# Arduino_extension_connectors.net
KiCad netlist of a schematic drawn in Altium Designer
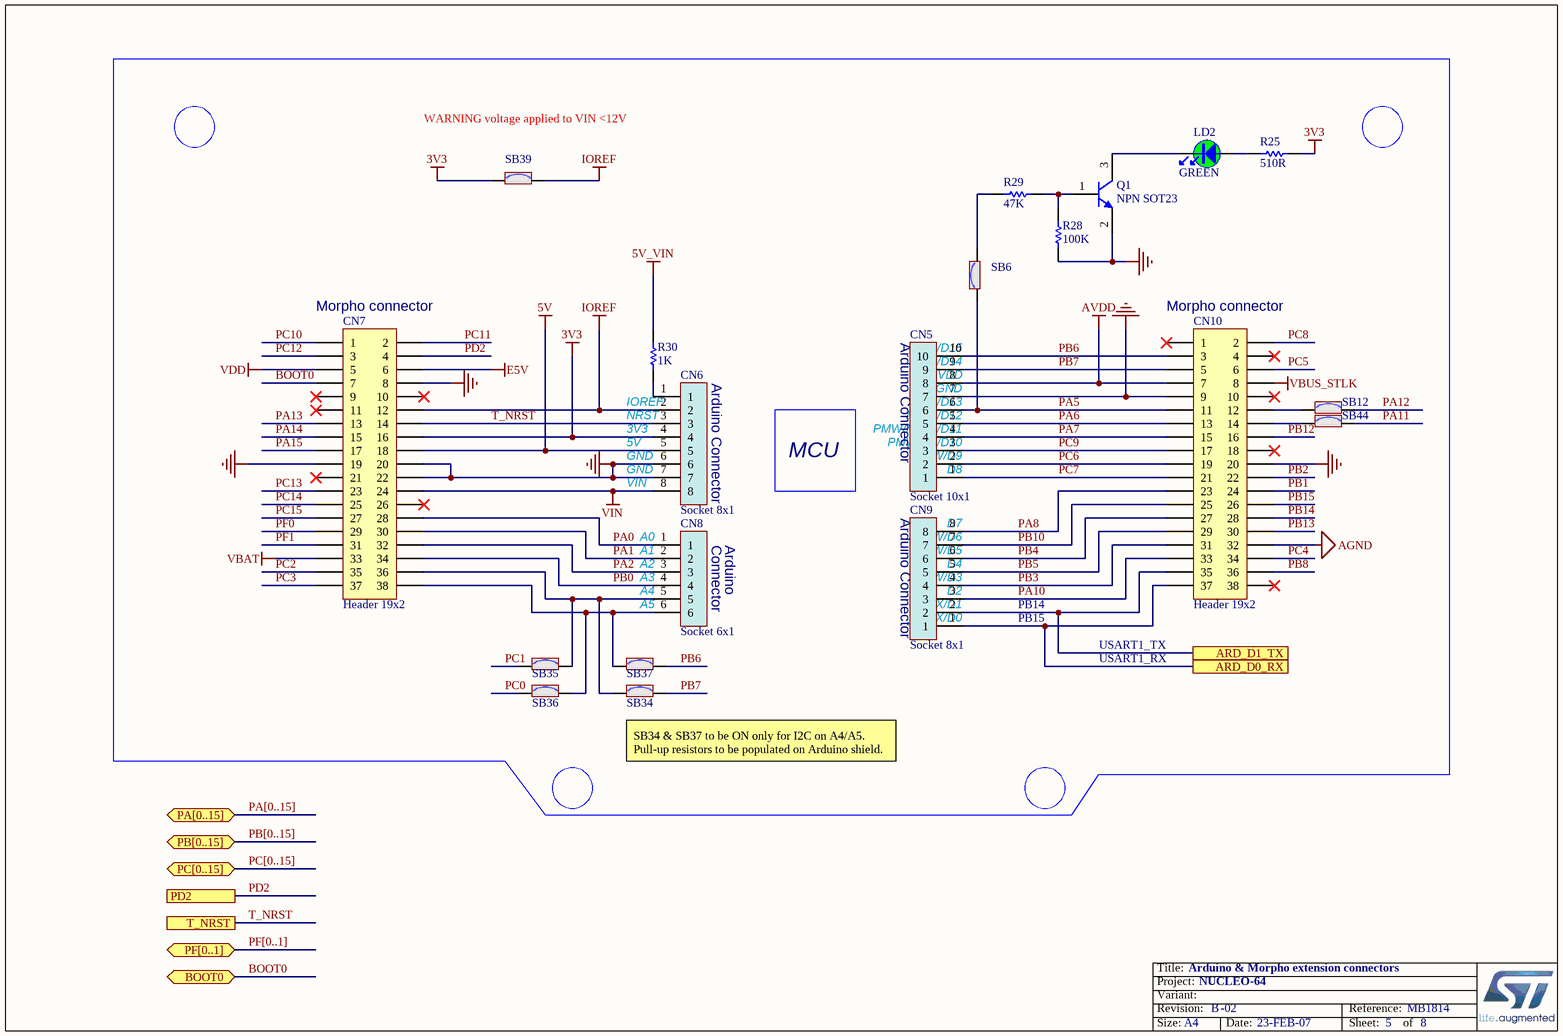
[diagram p0: Arduino_extension_connectors.SchDoc]

(export (version "E")
  (design (tool "Eeschema 10.0.6"))
  (components
    (comp (ref "CN5")
      (value "Socket 10x1")
      (footprint "CON_SAMTEC_SSQ-110-03-F-S")
      (description "Socket, 10x1, 2.54mm, VR, TH, T=8.51mm/10mm")
      (fields (field (name "INTERNAL_PART_NUMBER") "MCD-02625") (field (name "MANUFACTURER") "SAMTEC"))
      (libsource (lib "MCD_PARTS_database") (part "Socket 10x1"))
    )
    (comp (ref "CN6")
      (value "Socket 8x1")
      (footprint "CON_SAMTEC_SSQ-108-03-F-S")
      (description "Socket, 8x1, 2.54mm, VR, TH, T=8.51mm/10mm")
      (fields (field (name "INTERNAL_PART_NUMBER") "MCD-02624") (field (name "MANUFACTURER") "SAMTEC"))
      (libsource (lib "") (part "Socket 8x1_1"))
    )
    (comp (ref "CN7")
      (value "Header 19x2")
      (footprint "CON_SAMTEC_TSW-119-09-X-D")
      (description "Header, 19x2, 2,54mm, VR, TH, Height 5.84mm/10.16mm")
      (fields
        (field (name "INTERNAL_PART_NUMBER") "MCD-00213")
        (field (name "MANUFACTURER_PART_NUMBER") "TSW-119-09-x-D")
        (field (name "PROVIDED_BY") "SUBCO")
      )
      (libsource (lib "MCD_PARTS_database") (part "Header 19x2"))
    )
    (comp (ref "CN8")
      (value "Socket 6x1")
      (footprint "CON_SAMTEC_SSQ-106-03-F-S")
      (description "Socket, 6x1, 2.54mm, VR, TH, T=8.51mm/10mm")
      (fields (field (name "INTERNAL_PART_NUMBER") "MCD-02623") (field (name "MANUFACTURER") "SAMTEC"))
      (libsource (lib "MCD_PARTS_database") (part "Socket 6x1"))
    )
    (comp (ref "CN9")
      (value "Socket 8x1")
      (footprint "CON_SAMTEC_SSQ-108-03-F-S")
      (description "Socket, 8x1, 2.54mm, VR, TH, T=8.51mm/10mm")
      (fields (field (name "INTERNAL_PART_NUMBER") "MCD-02624") (field (name "MANUFACTURER") "SAMTEC"))
      (libsource (lib "MCD_PARTS_database") (part "Socket 8x1"))
    )
    (comp (ref "CN10")
      (value "Header 19x2")
      (footprint "CON_SAMTEC_TSW-119-09-X-D")
      (description "Header, 19x2, 2,54mm, VR, TH, Height 5.84mm/10.16mm")
      (fields
        (field (name "INTERNAL_PART_NUMBER") "MCD-00213")
        (field (name "MANUFACTURER_PART_NUMBER") "TSW-119-09-x-D")
        (field (name "PROVIDED_BY") "SUBCO")
      )
      (libsource (lib "MCD_PARTS_database") (part "Header 19x2"))
    )
    (comp (ref "LD2")
      (value "GREEN")
      (footprint "LED_0603_OSRAM_LG-Q396-PS-35_GREEN_1A2K_H0P4")
      (description "LED Green, 0603 SMD, Forward Voltage Typ=2V, Max=2.5V")
      (fields
        (field (name "INTERNAL_PART_NUMBER") "MCD-00588")
        (field (name "MANUFACTURER_PART_NUMBER") "LG Q396-PS-35")
        (field (name "PROVIDED_BY") "SUBCO")
      )
      (libsource (lib "MCD_PARTS_database") (part "LED_green"))
    )
    (comp (ref "Q1")
      (value "NPN SOT23")
      (footprint "NPN_SOT23")
      (description "NPN Bipolar Transistor")
      (fields
        (field (name "INTERNAL_PART_NUMBER") "MCD-00073")
        (field (name "MANUFACTURER_PART_NUMBER") "BSR14")
        (field (name "PROVIDED_BY") "SUBCO")
      )
      (libsource (lib "MCD_PARTS_database") (part "9013-SOT23"))
    )
    (comp (ref "R25")
      (value "510R")
      (footprint "R0603")
      (description "Resistor,510R,0603,1%,1/10W")
      (fields
        (field (name "INTERNAL_PART_NUMBER") "MCD-00225")
        (field (name "MANUFACTURER_PART_NUMBER") "RC0603FR-07510RL")
        (field (name "PROVIDED_BY") "SUBCO")
      )
      (libsource (lib "MCD_PARTS_database") (part "Resistor"))
    )
    (comp (ref "R28")
      (value "100K")
      (footprint "R0603")
      (description "Resistor,100K,0603,1%,1/10W")
      (fields
        (field (name "INTERNAL_PART_NUMBER") "MCD-00223")
        (field (name "MANUFACTURER_PART_NUMBER") "RC0603FR-07100KL")
        (field (name "PROVIDED_BY") "Subcon")
      )
      (libsource (lib "MCD_PARTS_database") (part "Resistor"))
    )
    (comp (ref "R29")
      (value "47K")
      (footprint "R0603")
      (description "Resistor,47K,0603,1%,1/10W")
      (fields
        (field (name "INTERNAL_PART_NUMBER") "MCD-00222")
        (field (name "MANUFACTURER_PART_NUMBER") "RC0603FR-0747KL")
        (field (name "PROVIDED_BY") "SUBCO")
      )
      (libsource (lib "MCD_PARTS_database") (part "Resistor"))
    )
    (comp (ref "R30")
      (value "1K")
      (footprint "R0603")
      (description "Resistor,1K,0603,1%,1/10W")
      (fields
        (field (name "INTERNAL_PART_NUMBER") "MCD-00070")
        (field (name "MANUFACTURER_PART_NUMBER") "RC0603FR-071KL")
        (field (name "PROVIDED_BY") "Subcon")
      )
      (libsource (lib "MCD_PARTS_database") (part "Resistor"))
    )
    (comp (ref "SB6")
      (value "~")
      (footprint "SOLDER-BRIDGE_R0603-0R")
      (description "Solder Bridge ON")
      (fields
        (field (name "INTERNAL_PART_NUMBER") "MCD-00071")
        (field (name "MANUFACTURER_PART_NUMBER") "RC0603JR-070RL")
        (field (name "PROVIDED_BY") "SUBCO")
      )
      (libsource (lib "") (part "SB_ON_1"))
    )
    (comp (ref "SB12")
      (value "~")
      (footprint "SOLDER-BRIDGE_R0603-0R")
      (description "Solder Bridge ON")
      (fields
        (field (name "INTERNAL_PART_NUMBER") "MCD-00071")
        (field (name "MANUFACTURER_PART_NUMBER") "RC0603JR-070RL")
        (field (name "PROVIDED_BY") "SUBCO")
      )
      (libsource (lib "MCD_PARTS_database") (part "SB_ON"))
    )
    (comp (ref "SB34")
      (value "~")
      (footprint "SOLDER-BRIDGE_R0603-0R")
      (description "Solder Bridge ON")
      (fields
        (field (name "INTERNAL_PART_NUMBER") "MCD-00071")
        (field (name "MANUFACTURER_PART_NUMBER") "RC0603JR-070RL")
        (field (name "PROVIDED_BY") "SUBCO")
      )
      (libsource (lib "MCD_PARTS_database") (part "SB_ON"))
    )
    (comp (ref "SB35")
      (value "~")
      (footprint "SOLDER-BRIDGE_R0603-0R")
      (description "Solder Bridge ON")
      (fields
        (field (name "INTERNAL_PART_NUMBER") "MCD-00071")
        (field (name "MANUFACTURER_PART_NUMBER") "RC0603JR-070RL")
        (field (name "PROVIDED_BY") "SUBCO")
      )
      (libsource (lib "MCD_PARTS_database") (part "SB_ON"))
    )
    (comp (ref "SB36")
      (value "~")
      (footprint "SOLDER-BRIDGE_R0603-0R")
      (description "Solder Bridge ON")
      (fields
        (field (name "INTERNAL_PART_NUMBER") "MCD-00071")
        (field (name "MANUFACTURER_PART_NUMBER") "RC0603JR-070RL")
        (field (name "PROVIDED_BY") "SUBCO")
      )
      (libsource (lib "MCD_PARTS_database") (part "SB_ON"))
    )
    (comp (ref "SB37")
      (value "~")
      (footprint "SOLDER-BRIDGE_R0603-0R")
      (description "Solder Bridge ON")
      (fields
        (field (name "INTERNAL_PART_NUMBER") "MCD-00071")
        (field (name "MANUFACTURER_PART_NUMBER") "RC0603JR-070RL")
        (field (name "PROVIDED_BY") "SUBCO")
      )
      (libsource (lib "MCD_PARTS_database") (part "SB_ON"))
    )
    (comp (ref "SB39")
      (value "~")
      (footprint "SOLDER-BRIDGE_R0603-0R")
      (description "Solder Bridge ON")
      (fields
        (field (name "INTERNAL_PART_NUMBER") "MCD-00071")
        (field (name "MANUFACTURER_PART_NUMBER") "RC0603JR-070RL")
        (field (name "PROVIDED_BY") "SUBCO")
      )
      (libsource (lib "MCD_PARTS_database") (part "SB_ON"))
    )
    (comp (ref "SB44")
      (value "~")
      (footprint "SOLDER-BRIDGE_R0603-0R")
      (description "Solder Bridge ON")
      (fields
        (field (name "INTERNAL_PART_NUMBER") "MCD-00071")
        (field (name "MANUFACTURER_PART_NUMBER") "RC0603JR-070RL")
        (field (name "PROVIDED_BY") "SUBCO")
      )
      (libsource (lib "MCD_PARTS_database") (part "SB_ON"))
    )
  )
  (nets
    (net (code "6") (name "/ARD_D0_RX") (class "Default")
      (node (ref "CN10") (pin "37") (pinfunction "37_37") (pintype "passive"))
      (node (ref "CN9") (pin "1") (pinfunction "1_1") (pintype "passive"))
    )
    (net (code "7") (name "/ARD_D1_TX") (class "Default")
      (node (ref "CN10") (pin "35") (pinfunction "35_35") (pintype "passive"))
      (node (ref "CN9") (pin "2") (pinfunction "2_2") (pintype "passive"))
    )
    (net (code "8") (name "/BOOT0") (class "Default")
      (node (ref "CN7") (pin "7") (pinfunction "7_7") (pintype "passive"))
    )
    (net (code "9") (name "/PA0") (class "Default")
      (node (ref "CN7") (pin "28") (pinfunction "28_28") (pintype "passive"))
      (node (ref "CN8") (pin "1") (pinfunction "1_1") (pintype "passive"))
    )
    (net (code "10") (name "/PA1") (class "Default")
      (node (ref "CN7") (pin "30") (pinfunction "30_30") (pintype "passive"))
      (node (ref "CN8") (pin "2") (pinfunction "2_2") (pintype "passive"))
    )
    (net (code "11") (name "/PA2") (class "Default")
      (node (ref "CN7") (pin "32") (pinfunction "32_32") (pintype "passive"))
      (node (ref "CN8") (pin "3") (pinfunction "3_3") (pintype "passive"))
    )
    (net (code "12") (name "/PA5") (class "Default")
      (node (ref "CN10") (pin "11") (pinfunction "11_11") (pintype "passive"))
      (node (ref "CN5") (pin "6") (pinfunction "6_6") (pintype "passive"))
      (node (ref "SB6") (pin "1") (pinfunction "1_1") (pintype "passive"))
    )
    (net (code "13") (name "/PA6") (class "Default")
      (node (ref "CN10") (pin "13") (pinfunction "13_13") (pintype "passive"))
      (node (ref "CN5") (pin "5") (pinfunction "5_5") (pintype "passive"))
    )
    (net (code "14") (name "/PA7") (class "Default")
      (node (ref "CN10") (pin "15") (pinfunction "15_15") (pintype "passive"))
      (node (ref "CN5") (pin "4") (pinfunction "4_4") (pintype "passive"))
    )
    (net (code "15") (name "/PA8") (class "Default")
      (node (ref "CN10") (pin "23") (pinfunction "23_23") (pintype "passive"))
      (node (ref "CN9") (pin "8") (pinfunction "8_8") (pintype "passive"))
    )
    (net (code "16") (name "/PA10") (class "Default")
      (node (ref "CN10") (pin "33") (pinfunction "33_33") (pintype "passive"))
      (node (ref "CN9") (pin "3") (pinfunction "3_3") (pintype "passive"))
    )
    (net (code "17") (name "/PA11") (class "Default")
      (node (ref "SB44") (pin "2") (pinfunction "2_2") (pintype "passive"))
    )
    (net (code "18") (name "/PA12") (class "Default")
      (node (ref "SB12") (pin "2") (pinfunction "2_2") (pintype "passive"))
    )
    (net (code "19") (name "/PA13") (class "Default")
      (node (ref "CN7") (pin "13") (pinfunction "13_13") (pintype "passive"))
    )
    (net (code "20") (name "/PA14") (class "Default")
      (node (ref "CN7") (pin "15") (pinfunction "15_15") (pintype "passive"))
    )
    (net (code "21") (name "/PA15") (class "Default")
      (node (ref "CN7") (pin "17") (pinfunction "17_17") (pintype "passive"))
    )
    (net (code "23") (name "/PB0") (class "Default")
      (node (ref "CN7") (pin "34") (pinfunction "34_34") (pintype "passive"))
      (node (ref "CN8") (pin "4") (pinfunction "4_4") (pintype "passive"))
    )
    (net (code "24") (name "/PB1") (class "Default")
      (node (ref "CN10") (pin "24") (pinfunction "24_24") (pintype "passive"))
    )
    (net (code "25") (name "/PB2") (class "Default")
      (node (ref "CN10") (pin "22") (pinfunction "22_22") (pintype "passive"))
    )
    (net (code "26") (name "/PB3") (class "Default")
      (node (ref "CN10") (pin "31") (pinfunction "31_31") (pintype "passive"))
      (node (ref "CN9") (pin "4") (pinfunction "4_4") (pintype "passive"))
    )
    (net (code "27") (name "/PB4") (class "Default")
      (node (ref "CN10") (pin "27") (pinfunction "27_27") (pintype "passive"))
      (node (ref "CN9") (pin "6") (pinfunction "6_6") (pintype "passive"))
    )
    (net (code "28") (name "/PB5") (class "Default")
      (node (ref "CN10") (pin "29") (pinfunction "29_29") (pintype "passive"))
      (node (ref "CN9") (pin "5") (pinfunction "5_5") (pintype "passive"))
    )
    (net (code "29") (name "/PB6") (class "Default")
      (node (ref "CN10") (pin "3") (pinfunction "3_3") (pintype "passive"))
      (node (ref "CN5") (pin "10") (pinfunction "10_10") (pintype "passive"))
      (node (ref "SB37") (pin "2") (pinfunction "2_2") (pintype "passive"))
    )
    (net (code "30") (name "/PB7") (class "Default")
      (node (ref "CN10") (pin "5") (pinfunction "5_5") (pintype "passive"))
      (node (ref "CN5") (pin "9") (pinfunction "9_9") (pintype "passive"))
      (node (ref "SB34") (pin "2") (pinfunction "2_2") (pintype "passive"))
    )
    (net (code "31") (name "/PB8") (class "Default")
      (node (ref "CN10") (pin "36") (pinfunction "36_36") (pintype "passive"))
    )
    (net (code "32") (name "/PB10") (class "Default")
      (node (ref "CN10") (pin "25") (pinfunction "25_25") (pintype "passive"))
      (node (ref "CN9") (pin "7") (pinfunction "7_7") (pintype "passive"))
    )
    (net (code "33") (name "/PB12") (class "Default")
      (node (ref "CN10") (pin "16") (pinfunction "16_16") (pintype "passive"))
    )
    (net (code "34") (name "/PB13") (class "Default")
      (node (ref "CN10") (pin "30") (pinfunction "30_30") (pintype "passive"))
    )
    (net (code "35") (name "/PB14") (class "Default")
      (node (ref "CN10") (pin "28") (pinfunction "28_28") (pintype "passive"))
    )
    (net (code "36") (name "/PB15") (class "Default")
      (node (ref "CN10") (pin "26") (pinfunction "26_26") (pintype "passive"))
    )
    (net (code "38") (name "/PC0") (class "Default")
      (node (ref "SB36") (pin "1") (pinfunction "1_1") (pintype "passive"))
    )
    (net (code "39") (name "/PC1") (class "Default")
      (node (ref "SB35") (pin "1") (pinfunction "1_1") (pintype "passive"))
    )
    (net (code "40") (name "/PC2") (class "Default")
      (node (ref "CN7") (pin "35") (pinfunction "35_35") (pintype "passive"))
    )
    (net (code "41") (name "/PC3") (class "Default")
      (node (ref "CN7") (pin "37") (pinfunction "37_37") (pintype "passive"))
    )
    (net (code "42") (name "/PC4") (class "Default")
      (node (ref "CN10") (pin "34") (pinfunction "34_34") (pintype "passive"))
    )
    (net (code "43") (name "/PC5") (class "Default")
      (node (ref "CN10") (pin "6") (pinfunction "6_6") (pintype "passive"))
    )
    (net (code "44") (name "/PC6") (class "Default")
      (node (ref "CN10") (pin "19") (pinfunction "19_19") (pintype "passive"))
      (node (ref "CN5") (pin "2") (pinfunction "2_2") (pintype "passive"))
    )
    (net (code "45") (name "/PC7") (class "Default")
      (node (ref "CN10") (pin "21") (pinfunction "21_21") (pintype "passive"))
      (node (ref "CN5") (pin "1") (pinfunction "1_1") (pintype "passive"))
    )
    (net (code "46") (name "/PC8") (class "Default")
      (node (ref "CN10") (pin "2") (pinfunction "2_2") (pintype "passive"))
    )
    (net (code "47") (name "/PC9") (class "Default")
      (node (ref "CN10") (pin "17") (pinfunction "17_17") (pintype "passive"))
      (node (ref "CN5") (pin "3") (pinfunction "3_3") (pintype "passive"))
    )
    (net (code "48") (name "/PC10") (class "Default")
      (node (ref "CN7") (pin "1") (pinfunction "1_1") (pintype "passive"))
    )
    (net (code "49") (name "/PC11") (class "Default")
      (node (ref "CN7") (pin "2") (pinfunction "2_2") (pintype "passive"))
    )
    (net (code "50") (name "/PC12") (class "Default")
      (node (ref "CN7") (pin "3") (pinfunction "3_3") (pintype "passive"))
    )
    (net (code "51") (name "/PC13") (class "Default")
      (node (ref "CN7") (pin "23") (pinfunction "23_23") (pintype "passive"))
    )
    (net (code "52") (name "/PC14") (class "Default")
      (node (ref "CN7") (pin "25") (pinfunction "25_25") (pintype "passive"))
    )
    (net (code "53") (name "/PC15") (class "Default")
      (node (ref "CN7") (pin "27") (pinfunction "27_27") (pintype "passive"))
    )
    (net (code "55") (name "/PD2") (class "Default")
      (node (ref "CN7") (pin "4") (pinfunction "4_4") (pintype "passive"))
    )
    (net (code "56") (name "/PF0") (class "Default")
      (node (ref "CN7") (pin "29") (pinfunction "29_29") (pintype "passive"))
    )
    (net (code "57") (name "/PF1") (class "Default")
      (node (ref "CN7") (pin "31") (pinfunction "31_31") (pintype "passive"))
    )
    (net (code "59") (name "/T_NRST") (class "Default")
      (node (ref "CN6") (pin "3") (pinfunction "3_3") (pintype "passive"))
      (node (ref "CN7") (pin "14") (pinfunction "14_14") (pintype "passive"))
    )
    (net (code "60") (name "3V3") (class "Default")
      (node (ref "CN6") (pin "4") (pinfunction "4_4") (pintype "passive"))
      (node (ref "CN7") (pin "16") (pinfunction "16_16") (pintype "passive"))
      (node (ref "R25") (pin "1") (pinfunction "1_1") (pintype "passive"))
      (node (ref "SB39") (pin "1") (pinfunction "1_1") (pintype "passive"))
    )
    (net (code "61") (name "5V") (class "Default")
      (node (ref "CN6") (pin "5") (pinfunction "5_5") (pintype "passive"))
      (node (ref "CN7") (pin "18") (pinfunction "18_18") (pintype "passive"))
    )
    (net (code "62") (name "5V_VIN") (class "Default")
      (node (ref "R30") (pin "2") (pinfunction "2_2") (pintype "passive"))
    )
    (net (code "63") (name "AGND") (class "Default")
      (node (ref "CN10") (pin "32") (pinfunction "32_32") (pintype "passive"))
    )
    (net (code "64") (name "AVDD") (class "Default")
      (node (ref "CN10") (pin "7") (pinfunction "7_7") (pintype "passive"))
      (node (ref "CN5") (pin "8") (pinfunction "8_8") (pintype "passive"))
    )
    (net (code "65") (name "E5V") (class "Default")
      (node (ref "CN7") (pin "6") (pinfunction "6_6") (pintype "passive"))
    )
    (net (code "66") (name "GND") (class "Default")
      (node (ref "CN10") (pin "20") (pinfunction "20_20") (pintype "passive"))
      (node (ref "CN10") (pin "9") (pinfunction "9_9") (pintype "passive"))
      (node (ref "CN5") (pin "7") (pinfunction "7_7") (pintype "passive"))
      (node (ref "CN6") (pin "6") (pinfunction "6_6") (pintype "passive"))
      (node (ref "CN6") (pin "7") (pinfunction "7_7") (pintype "passive"))
      (node (ref "CN7") (pin "19") (pinfunction "19_19") (pintype "passive"))
      (node (ref "CN7") (pin "20") (pinfunction "20_20") (pintype "passive"))
      (node (ref "CN7") (pin "22") (pinfunction "22_22") (pintype "passive"))
      (node (ref "CN7") (pin "8") (pinfunction "8_8") (pintype "passive"))
      (node (ref "Q1") (pin "2") (pinfunction "E_2") (pintype "passive"))
      (node (ref "R28") (pin "1") (pinfunction "1_1") (pintype "passive"))
    )
    (net (code "67") (name "IOREF") (class "Default")
      (node (ref "CN6") (pin "2") (pinfunction "2_2") (pintype "passive"))
      (node (ref "CN7") (pin "12") (pinfunction "12_12") (pintype "passive"))
      (node (ref "SB39") (pin "2") (pinfunction "2_2") (pintype "passive"))
    )
    (net (code "68") (name "Net-(CN6-Pad1)") (class "Default")
      (node (ref "CN6") (pin "1") (pinfunction "1_1") (pintype "passive"))
      (node (ref "R30") (pin "1") (pinfunction "1_1") (pintype "passive"))
    )
    (net (code "69") (name "Net-(CN7-Pad36)") (class "Default")
      (node (ref "CN7") (pin "36") (pinfunction "36_36") (pintype "passive"))
      (node (ref "CN8") (pin "5") (pinfunction "5_5") (pintype "passive"))
      (node (ref "SB34") (pin "1") (pinfunction "1_1") (pintype "passive"))
      (node (ref "SB35") (pin "2") (pinfunction "2_2") (pintype "passive"))
    )
    (net (code "70") (name "Net-(CN7-Pad38)") (class "Default")
      (node (ref "CN7") (pin "38") (pinfunction "38_38") (pintype "passive"))
      (node (ref "CN8") (pin "6") (pinfunction "6_6") (pintype "passive"))
      (node (ref "SB36") (pin "2") (pinfunction "2_2") (pintype "passive"))
      (node (ref "SB37") (pin "1") (pinfunction "1_1") (pintype "passive"))
    )
    (net (code "71") (name "Net-(CN10-Pad12)") (class "Default")
      (node (ref "CN10") (pin "12") (pinfunction "12_12") (pintype "passive"))
      (node (ref "SB12") (pin "1") (pinfunction "1_1") (pintype "passive"))
    )
    (net (code "72") (name "Net-(CN10-Pad14)") (class "Default")
      (node (ref "CN10") (pin "14") (pinfunction "14_14") (pintype "passive"))
      (node (ref "SB44") (pin "1") (pinfunction "1_1") (pintype "passive"))
    )
    (net (code "73") (name "Net-(LD2-Pad1)") (class "Default")
      (node (ref "LD2") (pin "1") (pintype "passive"))
      (node (ref "R25") (pin "2") (pinfunction "2_2") (pintype "passive"))
    )
    (net (code "74") (name "Net-(Q1-B)") (class "Default")
      (node (ref "Q1") (pin "1") (pinfunction "B_1") (pintype "passive"))
      (node (ref "R28") (pin "2") (pinfunction "2_2") (pintype "passive"))
      (node (ref "R29") (pin "2") (pinfunction "2_2") (pintype "passive"))
    )
    (net (code "75") (name "Net-(Q1-C)") (class "Default")
      (node (ref "LD2") (pin "2") (pintype "passive"))
      (node (ref "Q1") (pin "3") (pinfunction "C_3") (pintype "passive"))
    )
    (net (code "76") (name "Net-(R29-Pad1)") (class "Default")
      (node (ref "R29") (pin "1") (pinfunction "1_1") (pintype "passive"))
      (node (ref "SB6") (pin "2") (pinfunction "2_2") (pintype "passive"))
    )
    (net (code "77") (name "VBAT") (class "Default")
      (node (ref "CN7") (pin "33") (pinfunction "33_33") (pintype "passive"))
    )
    (net (code "78") (name "VBUS_STLK") (class "Default")
      (node (ref "CN10") (pin "8") (pinfunction "8_8") (pintype "passive"))
    )
    (net (code "79") (name "VDD") (class "Default")
      (node (ref "CN7") (pin "5") (pinfunction "5_5") (pintype "passive"))
    )
    (net (code "80") (name "VIN") (class "Default")
      (node (ref "CN6") (pin "8") (pinfunction "8_8") (pintype "passive"))
      (node (ref "CN7") (pin "24") (pinfunction "24_24") (pintype "passive"))
    )
    (net (code "81") (name "unconnected-(CN7-Pad9)") (class "Default")
      (node (ref "CN7") (pin "9") (pinfunction "9_9") (pintype "passive+no_connect"))
    )
    (net (code "82") (name "unconnected-(CN7-Pad10)") (class "Default")
      (node (ref "CN7") (pin "10") (pinfunction "10_10") (pintype "passive+no_connect"))
    )
    (net (code "83") (name "unconnected-(CN7-Pad11)") (class "Default")
      (node (ref "CN7") (pin "11") (pinfunction "11_11") (pintype "passive+no_connect"))
    )
    (net (code "84") (name "unconnected-(CN7-Pad21)") (class "Default")
      (node (ref "CN7") (pin "21") (pinfunction "21_21") (pintype "passive+no_connect"))
    )
    (net (code "85") (name "unconnected-(CN7-Pad26)") (class "Default")
      (node (ref "CN7") (pin "26") (pinfunction "26_26") (pintype "passive+no_connect"))
    )
    (net (code "86") (name "unconnected-(CN10-Pad1)") (class "Default")
      (node (ref "CN10") (pin "1") (pinfunction "1_1") (pintype "passive+no_connect"))
    )
    (net (code "87") (name "unconnected-(CN10-Pad4)") (class "Default")
      (node (ref "CN10") (pin "4") (pinfunction "4_4") (pintype "passive+no_connect"))
    )
    (net (code "88") (name "unconnected-(CN10-Pad10)") (class "Default")
      (node (ref "CN10") (pin "10") (pinfunction "10_10") (pintype "passive+no_connect"))
    )
    (net (code "89") (name "unconnected-(CN10-Pad18)") (class "Default")
      (node (ref "CN10") (pin "18") (pinfunction "18_18") (pintype "passive+no_connect"))
    )
    (net (code "90") (name "unconnected-(CN10-Pad38)") (class "Default")
      (node (ref "CN10") (pin "38") (pinfunction "38_38") (pintype "passive+no_connect"))
    )
  )
)
